# DC_Motor_SCH.net
KiCad netlist of a schematic drawn in Altium Designer
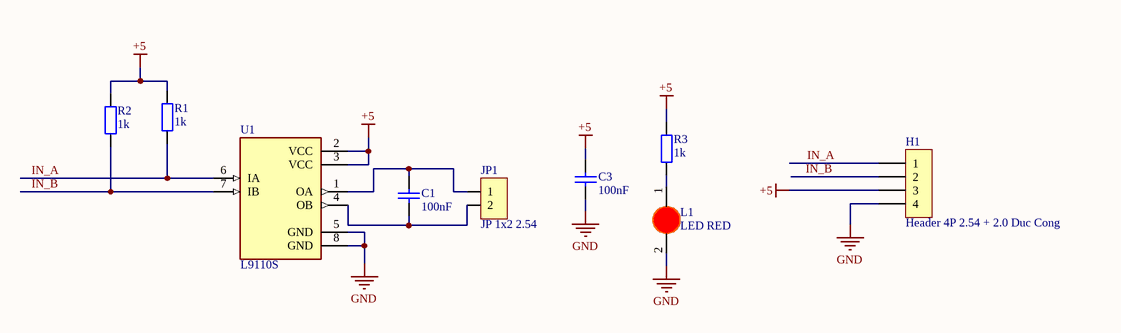
[diagram p0: DC Motor_SCH.SchDoc]

(export (version "E")
  (design (tool "Eeschema 10.0.6"))
  (components
    (comp (ref "C1")
      (value "100nF")
      (footprint "tu 0603")
      (description "Dán")
      (libsource (lib "namnt_Lib") (part "Tu 0603 104 50V 10%"))
    )
    (comp (ref "C3")
      (value "100nF")
      (footprint "tu 0603")
      (description "Dán")
      (libsource (lib "namnt_Lib") (part "Tu 0603 104 50V 10%"))
    )
    (comp (ref "H1")
      (value "Header 4P 2.54 + 2.0 Duc Cong")
      (footprint "Header 4P DC 2.54 + 2.0")
      (description "Cắm")
      (libsource (lib "namnt_Lib") (part "Header 4P 2.54 + 2.0 Duc Cong"))
    )
    (comp (ref "JP1")
      (value "JP 1x2 2.54")
      (footprint "JP 1x2 DT")
      (description "Cắm")
      (libsource (lib "namnt_Lib") (part "JP 1x2 2.54 Duc Thang"))
    )
    (comp (ref "L1")
      (value "LED RED")
      (footprint "LED-0805-Red")
      (description "Dán")
      (libsource (lib "namnt_Lib") (part "LED 0805 Do"))
    )
    (comp (ref "R1")
      (value "1k")
      (footprint "tro smd 0603")
      (description "Dán")
      (libsource (lib "namnt_Lib") (part "Tro 0603 1% 1k"))
    )
    (comp (ref "R2")
      (value "1k")
      (footprint "tro smd 0603")
      (description "Dán")
      (libsource (lib "namnt_Lib") (part "Tro 0603 1% 1k"))
    )
    (comp (ref "R3")
      (value "1k")
      (footprint "tro smd 0603")
      (description "Dán")
      (libsource (lib "namnt_Lib") (part "Tro 0603 1% 1k"))
    )
    (comp (ref "U1")
      (value "L9110S")
      (footprint "SOIC127P599X172-8N")
      (description "SOP-8 MOTOR DRIVER ICS ROHS")
      (fields (field (name "MF") "ON Semiconductor"))
      (libsource (lib "namnt_Lib") (part "L9110S"))
    )
  )
  (nets
    (net (code "1") (name "+5") (class "Default")
      (node (ref "C3") (pin "1") (pinfunction "1_1") (pintype "passive"))
      (node (ref "H1") (pin "3") (pinfunction "3_3") (pintype "passive"))
      (node (ref "R1") (pin "2") (pinfunction "2_2") (pintype "passive"))
      (node (ref "R2") (pin "2") (pinfunction "2_2") (pintype "passive"))
      (node (ref "R3") (pin "2") (pinfunction "2_2") (pintype "passive"))
      (node (ref "U1") (pin "2") (pinfunction "VCC_2") (pintype "power_in"))
      (node (ref "U1") (pin "3") (pinfunction "VCC_3") (pintype "power_in"))
    )
    (net (code "2") (name "/IN_A") (class "Default")
      (node (ref "H1") (pin "1") (pinfunction "1_1") (pintype "passive"))
      (node (ref "R1") (pin "1") (pinfunction "1_1") (pintype "passive"))
      (node (ref "U1") (pin "6") (pinfunction "IA_6") (pintype "input"))
    )
    (net (code "3") (name "/IN_B") (class "Default")
      (node (ref "H1") (pin "2") (pinfunction "2_2") (pintype "passive"))
      (node (ref "R2") (pin "1") (pinfunction "1_1") (pintype "passive"))
      (node (ref "U1") (pin "7") (pinfunction "IB_7") (pintype "input"))
    )
    (net (code "4") (name "GND") (class "Default")
      (node (ref "C3") (pin "2") (pinfunction "2_2") (pintype "passive"))
      (node (ref "H1") (pin "4") (pinfunction "4_4") (pintype "passive"))
      (node (ref "L1") (pin "2") (pinfunction "K_2") (pintype "passive"))
      (node (ref "U1") (pin "5") (pinfunction "GND_5") (pintype "power_in"))
      (node (ref "U1") (pin "8") (pinfunction "GND_8") (pintype "power_in"))
    )
    (net (code "5") (name "Net-(L1-A)") (class "Default")
      (node (ref "L1") (pin "1") (pinfunction "A_1") (pintype "passive"))
      (node (ref "R3") (pin "1") (pinfunction "1_1") (pintype "passive"))
    )
    (net (code "6") (name "Net-(U1-OA)") (class "Default")
      (node (ref "C1") (pin "1") (pinfunction "1_1") (pintype "passive"))
      (node (ref "JP1") (pin "1") (pinfunction "1_1") (pintype "passive"))
      (node (ref "U1") (pin "1") (pinfunction "OA_1") (pintype "output"))
    )
    (net (code "7") (name "Net-(U1-OB)") (class "Default")
      (node (ref "C1") (pin "2") (pinfunction "2_2") (pintype "passive"))
      (node (ref "JP1") (pin "2") (pinfunction "2_2") (pintype "passive"))
      (node (ref "U1") (pin "4") (pinfunction "OB_4") (pintype "output"))
    )
  )
)
